# power_protection.net
KiCad netlist of a schematic drawn in Altium Designer
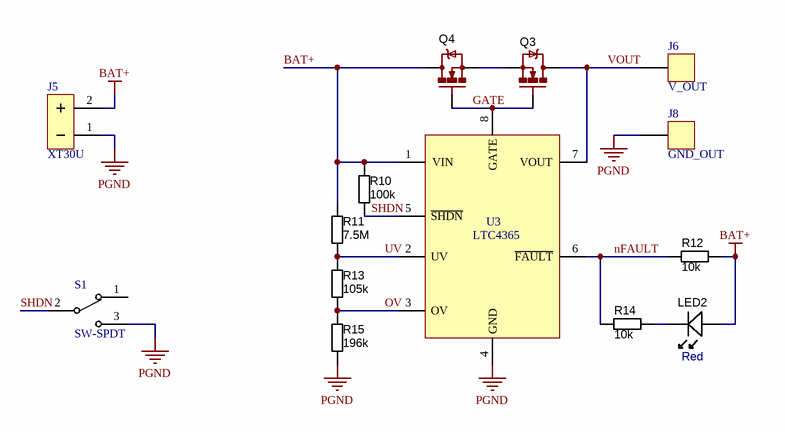
[diagram p0: power_protection.SchDoc]

(export (version "E")
  (design (tool "Eeschema 10.0.6"))
  (components
    (comp (ref "J5")
      (value "XT30U")
      (footprint "XT30U-PCB-LA-CUTOUT")
      (libsource (lib "connectors") (part "XT30U"))
    )
    (comp (ref "J6") (value "V_OUT") (footprint "POWER-PAD") (libsource (lib "connectors") (part "HEADER-1")))
    (comp (ref "J8")
      (value "GND_OUT")
      (footprint "POWER-PAD")
      (libsource (lib "connectors") (part "HEADER-1"))
    )
    (comp (ref "LED2")
      (value "Red")
      (footprint "LED-0603-GREEN")
      (description "LED 0603 SMD Green 525nm 350mcd 20mA")
      (libsource (lib "PBL - Light Sources") (part "LED_SMD_Green_0603_525nm_350mcd"))
    )
    (comp (ref "Q3") (value "MOSFET-N") (footprint "SOT669") (libsource (lib "mosfets") (part "MOSFET-N")))
    (comp (ref "Q4") (value "MOSFET-N") (footprint "SOT669") (libsource (lib "") (part "MOSFET-N_1")))
    (comp (ref "R10")
      (value "100k")
      (footprint "RESC1608X55N")
      (description "Resistor SMD chip 1.5k Ohm 0.1W 5% 0603")
      (fields (field (name "TOLERANCE") "±5%"))
      (libsource (lib "") (part "RES_1K5_0603_5%_1"))
    )
    (comp (ref "R11")
      (value "7.5M")
      (footprint "RESC1608X55N")
      (description "Resistor SMD chip 1.5k Ohm 0.1W 5% 0603")
      (fields (field (name "TOLERANCE") "±5%"))
      (libsource (lib "") (part "RES_1K5_0603_5%_1"))
    )
    (comp (ref "R12")
      (value "10k")
      (footprint "RESC1608X55N")
      (description "Resistor SMD chip 1.5k Ohm 0.1W 5% 0603")
      (fields (field (name "TOLERANCE") "±5%"))
      (libsource (lib "PBL - Resistors") (part "RES_1K5_0603_5%"))
    )
    (comp (ref "R13")
      (value "105k")
      (footprint "RESC1608X55N")
      (description "Resistor SMD chip 1.5k Ohm 0.1W 5% 0603")
      (fields (field (name "TOLERANCE") "±5%"))
      (libsource (lib "") (part "RES_1K5_0603_5%_1"))
    )
    (comp (ref "R14")
      (value "10k")
      (footprint "RESC1608X55N")
      (description "Resistor SMD chip 1.5k Ohm 0.1W 5% 0603")
      (fields (field (name "TOLERANCE") "±5%"))
      (libsource (lib "PBL - Resistors") (part "RES_1K5_0603_5%"))
    )
    (comp (ref "R15")
      (value "196k")
      (footprint "RESC1608X55N")
      (description "Resistor SMD chip 1.5k Ohm 0.1W 5% 0603")
      (fields (field (name "TOLERANCE") "±5%"))
      (libsource (lib "") (part "RES_1K5_0603_5%_1"))
    )
    (comp (ref "S1")
      (value "SW-SPDT")
      (footprint "A12AP-PCB-CUTOUT")
      (libsource (lib "switches") (part "SW-SPDT"))
    )
    (comp (ref "U3") (value "LTC4365") (footprint "SOT23-8") (libsource (lib "power") (part "LTC4365")))
  )
  (nets
    (net (code "1") (name "/GATE") (class "Default")
      (node (ref "Q3") (pin "G") (pinfunction "G_G") (pintype "passive"))
      (node (ref "Q4") (pin "G") (pinfunction "G_G") (pintype "passive"))
      (node (ref "U3") (pin "8") (pinfunction "GATE_8") (pintype "passive"))
    )
    (net (code "2") (name "/OV") (class "Default")
      (node (ref "R13") (pin "1") (pinfunction "1_1") (pintype "passive"))
      (node (ref "R15") (pin "2") (pinfunction "2_2") (pintype "passive"))
      (node (ref "U3") (pin "3") (pinfunction "OV_3") (pintype "passive"))
    )
    (net (code "3") (name "/SHDN") (class "Default")
      (node (ref "R10") (pin "1") (pinfunction "1_1") (pintype "passive"))
      (node (ref "S1") (pin "2") (pinfunction "2_2") (pintype "passive"))
      (node (ref "U3") (pin "5") (pinfunction "~{SHDN}_5") (pintype "passive"))
    )
    (net (code "4") (name "/UV") (class "Default")
      (node (ref "R11") (pin "1") (pinfunction "1_1") (pintype "passive"))
      (node (ref "R13") (pin "2") (pinfunction "2_2") (pintype "passive"))
      (node (ref "U3") (pin "2") (pinfunction "UV_2") (pintype "passive"))
    )
    (net (code "5") (name "/VOUT") (class "Default")
      (node (ref "J6") (pin "1") (pinfunction "1_1") (pintype "passive"))
      (node (ref "Q3") (pin "D") (pinfunction "D_D") (pintype "passive"))
      (node (ref "U3") (pin "7") (pinfunction "VOUT_7") (pintype "passive"))
    )
    (net (code "6") (name "/nFAULT") (class "Default")
      (node (ref "R12") (pin "1") (pinfunction "1_1") (pintype "passive"))
      (node (ref "R14") (pin "1") (pinfunction "1_1") (pintype "passive"))
      (node (ref "U3") (pin "6") (pinfunction "~{FAULT}_6") (pintype "passive"))
    )
    (net (code "7") (name "BAT+") (class "Default")
      (node (ref "J5") (pin "2") (pinfunction "+_2") (pintype "passive"))
      (node (ref "LED2") (pin "A") (pinfunction "A_A") (pintype "passive"))
      (node (ref "Q4") (pin "D") (pinfunction "D_D") (pintype "passive"))
      (node (ref "R10") (pin "2") (pinfunction "2_2") (pintype "passive"))
      (node (ref "R11") (pin "2") (pinfunction "2_2") (pintype "passive"))
      (node (ref "R12") (pin "2") (pinfunction "2_2") (pintype "passive"))
      (node (ref "U3") (pin "1") (pinfunction "VIN_1") (pintype "passive"))
    )
    (net (code "8") (name "Net-(LED2-PadK)") (class "Default")
      (node (ref "LED2") (pin "K") (pinfunction "K_K") (pintype "passive"))
      (node (ref "R14") (pin "2") (pinfunction "2_2") (pintype "passive"))
    )
    (net (code "9") (name "Net-(Q3-PadS)") (class "Default")
      (node (ref "Q3") (pin "S") (pinfunction "S_S") (pintype "passive"))
      (node (ref "Q4") (pin "S") (pinfunction "S_S") (pintype "passive"))
    )
    (net (code "10") (name "PGND") (class "Default")
      (node (ref "J5") (pin "1") (pinfunction "-_1") (pintype "passive"))
      (node (ref "J8") (pin "1") (pinfunction "1_1") (pintype "passive"))
      (node (ref "R15") (pin "1") (pinfunction "1_1") (pintype "passive"))
      (node (ref "S1") (pin "3") (pinfunction "3_3") (pintype "passive"))
      (node (ref "U3") (pin "4") (pinfunction "GND_4") (pintype "passive"))
    )
    (net (code "11") (name "unconnected-(S1-Pad1)") (class "Default")
      (node (ref "S1") (pin "1") (pinfunction "1_1") (pintype "passive"))
    )
  )
)
